# Digital_Inputs.net
KiCad netlist of a schematic drawn in Altium Designer
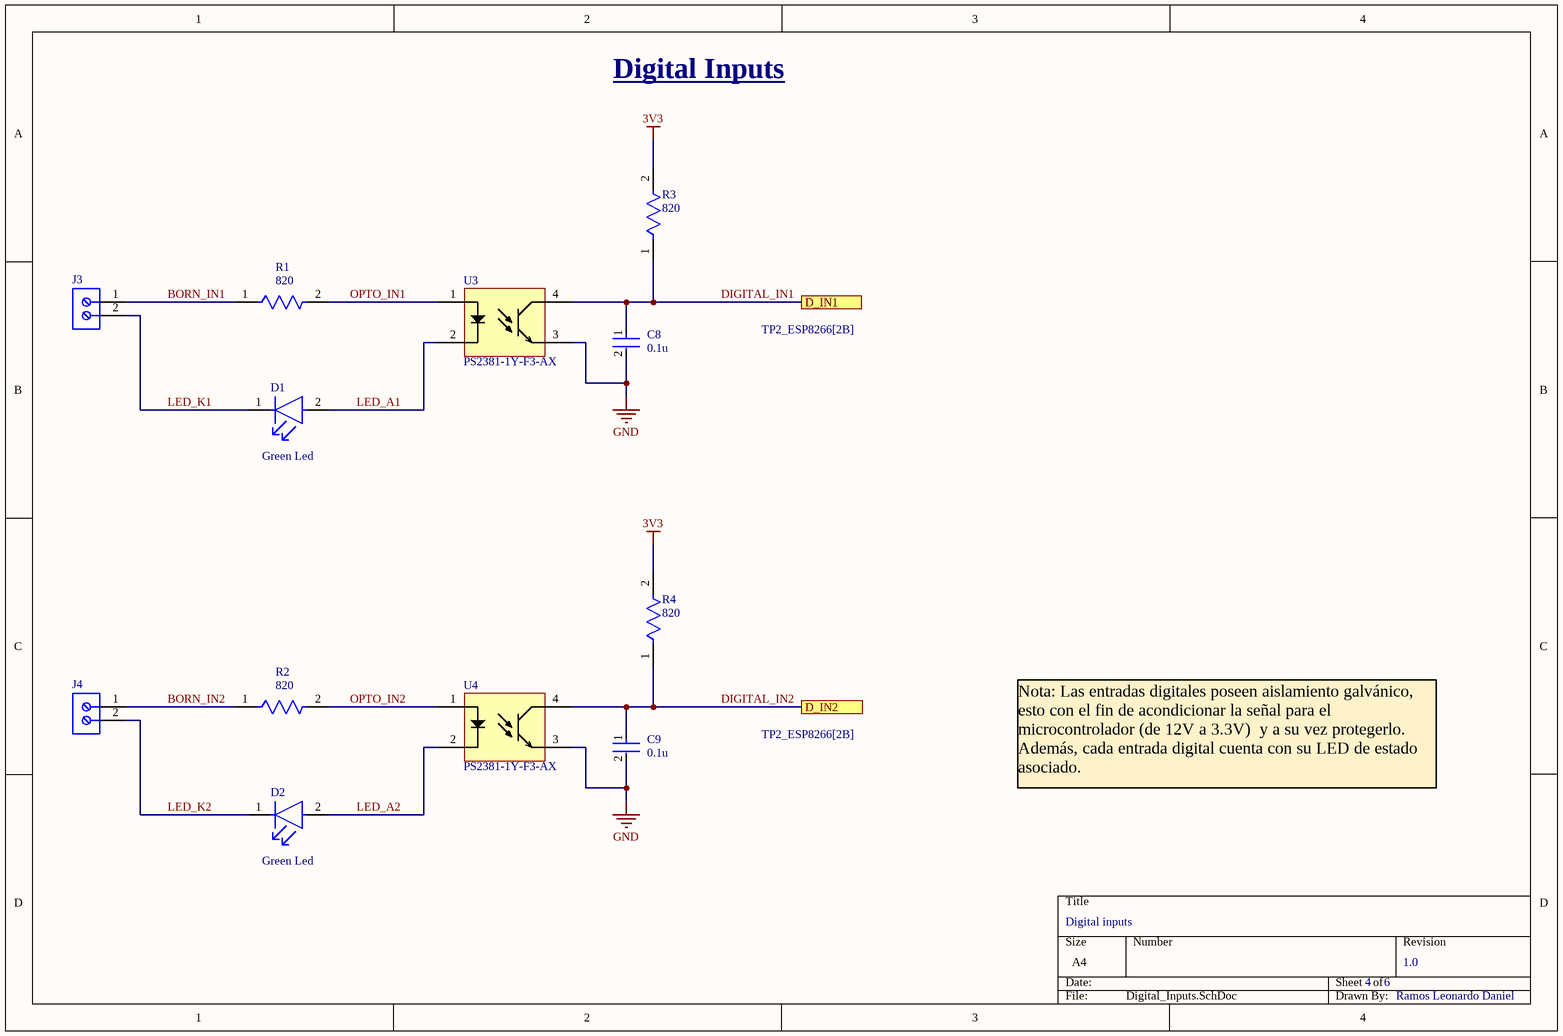
[diagram p0: Digital_Inputs.SchDoc]

(export (version "E")
  (design (tool "Eeschema 10.0.6"))
  (components
    (comp (ref "C8")
      (value "0.1u")
      (footprint "FP-CC0805-0_85-MFG")
      (description "CAP CER 0.1UF 25V X7R 0805")
      (fields (field (name "MANUFACTURER PART NUMBER") "CC0805KRX7R8BB104") (field (name "TOLERANCE") "0.1"))
      (libsource (lib "Altium Content Vault") (part "11868f565c42a9108669ba33697ecf6"))
    )
    (comp (ref "C9")
      (value "0.1u")
      (footprint "FP-CC0805-0_85-MFG")
      (description "CAP CER 0.1UF 25V X7R 0805")
      (fields (field (name "MANUFACTURER PART NUMBER") "CC0805KRX7R8BB104") (field (name "TOLERANCE") "0.1"))
      (libsource (lib "Altium Content Vault") (part "11868f565c42a9108669ba33697ecf6"))
    )
    (comp (ref "D1")
      (value "Green Led")
      (footprint "FP-LTST-C190GKT-MFG")
      (description "LED GREEN CLEAR CHIP SMD LTST-C190GKT")
      (fields (field (name "VOLTAGE") "2V"))
      (libsource (lib "Altium Content Vault") (part "8706943c75ba83719d021d2fdc84c58"))
    )
    (comp (ref "D2")
      (value "Green Led")
      (footprint "FP-LTST-C190GKT-MFG")
      (description "LED GREEN CLEAR CHIP SMD LTST-C190GKT")
      (fields (field (name "VOLTAGE") "2V"))
      (libsource (lib "Altium Content Vault") (part "8706943c75ba83719d021d2fdc84c58"))
    )
    (comp (ref "J3")
      (value "691137710002")
      (footprint "691137710002")
      (libsource (lib "Altium Content Vault") (part "TBL - 1R - 02P - Screw"))
    )
    (comp (ref "J4")
      (value "691137710002")
      (footprint "691137710002")
      (libsource (lib "Altium Content Vault") (part "TBL - 1R - 02P - Screw"))
    )
    (comp (ref "R1")
      (value "CRCW08054K70JNEA")
      (footprint "FP-CRCW0805-e3-IPC_B")
      (description "RES Thick Film, 4.7kΩ, 5%, 0.125W, 200ppm/°C, 0805")
      (fields (field (name "TOLERANCE") "5%") (field (name "RESISTANCE") "820"))
      (libsource (lib "Altium Content Vault") (part "1029c3af85768c4190bb7ad29bc67b5"))
    )
    (comp (ref "R2")
      (value "CRCW08054K70JNEA")
      (footprint "FP-CRCW0805-e3-IPC_B")
      (description "RES Thick Film, 4.7kΩ, 5%, 0.125W, 200ppm/°C, 0805")
      (fields (field (name "TOLERANCE") "5%") (field (name "RESISTANCE") "820"))
      (libsource (lib "Altium Content Vault") (part "1029c3af85768c4190bb7ad29bc67b5"))
    )
    (comp (ref "R3")
      (value "CRCW08054K70JNEA")
      (footprint "FP-CRCW0805-e3-IPC_B")
      (description "RES Thick Film, 4.7kΩ, 5%, 0.125W, 200ppm/°C, 0805")
      (fields (field (name "TOLERANCE") "5%") (field (name "RESISTANCE") "820"))
      (libsource (lib "Altium Content Vault") (part "1029c3af85768c4190bb7ad29bc67b5"))
    )
    (comp (ref "R4")
      (value "CRCW08054K70JNEA")
      (footprint "FP-CRCW0805-e3-IPC_B")
      (description "RES Thick Film, 4.7kΩ, 5%, 0.125W, 200ppm/°C, 0805")
      (fields (field (name "TOLERANCE") "5%") (field (name "RESISTANCE") "820"))
      (libsource (lib "Altium Content Vault") (part "1029c3af85768c4190bb7ad29bc67b5"))
    )
    (comp (ref "U3")
      (value "PS2381-1Y-F3-AX")
      (footprint "LSOP254P1020X230-4N")
      (description "PS2381-1Y-F3-AX Optocoupler, Transistor, 5Kv, Lsop-4 Rohs Compliant: Yes")
      (libsource (lib "Altium Content Vault") (part "PS2381-1Y-F3-AX"))
    )
    (comp (ref "U4")
      (value "PS2381-1Y-F3-AX")
      (footprint "LSOP254P1020X230-4N")
      (description "PS2381-1Y-F3-AX Optocoupler, Transistor, 5Kv, Lsop-4 Rohs Compliant: Yes")
      (libsource (lib "Altium Content Vault") (part "PS2381-1Y-F3-AX"))
    )
  )
  (nets
    (net (code "1") (name "/BORN_IN1") (class "Default")
      (node (ref "J3") (pin "1") (pinfunction "1_1") (pintype "passive"))
      (node (ref "R1") (pin "1") (pinfunction "1_1") (pintype "passive"))
    )
    (net (code "2") (name "/BORN_IN2") (class "Default")
      (node (ref "J4") (pin "1") (pinfunction "1_1") (pintype "passive"))
      (node (ref "R2") (pin "1") (pinfunction "1_1") (pintype "passive"))
    )
    (net (code "3") (name "/DIGITAL_IN1") (class "Default")
      (node (ref "C8") (pin "1") (pinfunction "1_1") (pintype "passive"))
      (node (ref "R3") (pin "1") (pinfunction "1_1") (pintype "passive"))
      (node (ref "U3") (pin "4") (pinfunction "Collector_4") (pintype "power_in"))
    )
    (net (code "4") (name "/DIGITAL_IN2") (class "Default")
      (node (ref "C9") (pin "1") (pinfunction "1_1") (pintype "passive"))
      (node (ref "R4") (pin "1") (pinfunction "1_1") (pintype "passive"))
      (node (ref "U4") (pin "4") (pinfunction "Collector_4") (pintype "power_in"))
    )
    (net (code "5") (name "/LED_A1") (class "Default")
      (node (ref "D1") (pin "2") (pinfunction "A_2") (pintype "passive"))
      (node (ref "U3") (pin "2") (pinfunction "Cathode_2") (pintype "passive"))
    )
    (net (code "6") (name "/LED_A2") (class "Default")
      (node (ref "D2") (pin "2") (pinfunction "A_2") (pintype "passive"))
      (node (ref "U4") (pin "2") (pinfunction "Cathode_2") (pintype "passive"))
    )
    (net (code "7") (name "/LED_K1") (class "Default")
      (node (ref "D1") (pin "1") (pinfunction "C_1") (pintype "passive"))
      (node (ref "J3") (pin "2") (pinfunction "2_2") (pintype "passive"))
    )
    (net (code "8") (name "/LED_K2") (class "Default")
      (node (ref "D2") (pin "1") (pinfunction "C_1") (pintype "passive"))
      (node (ref "J4") (pin "2") (pinfunction "2_2") (pintype "passive"))
    )
    (net (code "9") (name "/OPTO_IN1") (class "Default")
      (node (ref "R1") (pin "2") (pinfunction "2_2") (pintype "passive"))
      (node (ref "U3") (pin "1") (pinfunction "Anode_1") (pintype "passive"))
    )
    (net (code "10") (name "/OPTO_IN2") (class "Default")
      (node (ref "R2") (pin "2") (pinfunction "2_2") (pintype "passive"))
      (node (ref "U4") (pin "1") (pinfunction "Anode_1") (pintype "passive"))
    )
    (net (code "11") (name "3V3") (class "Default")
      (node (ref "R3") (pin "2") (pinfunction "2_2") (pintype "passive"))
      (node (ref "R4") (pin "2") (pinfunction "2_2") (pintype "passive"))
    )
    (net (code "12") (name "GND") (class "Default")
      (node (ref "C8") (pin "2") (pinfunction "2_2") (pintype "passive"))
      (node (ref "C9") (pin "2") (pinfunction "2_2") (pintype "passive"))
      (node (ref "U3") (pin "3") (pinfunction "Emitter_3") (pintype "power_in"))
      (node (ref "U4") (pin "3") (pinfunction "Emitter_3") (pintype "power_in"))
    )
  )
)
